# Circuit_Etudiant_2023.net
KiCad netlist of a schematic drawn in Altium Designer
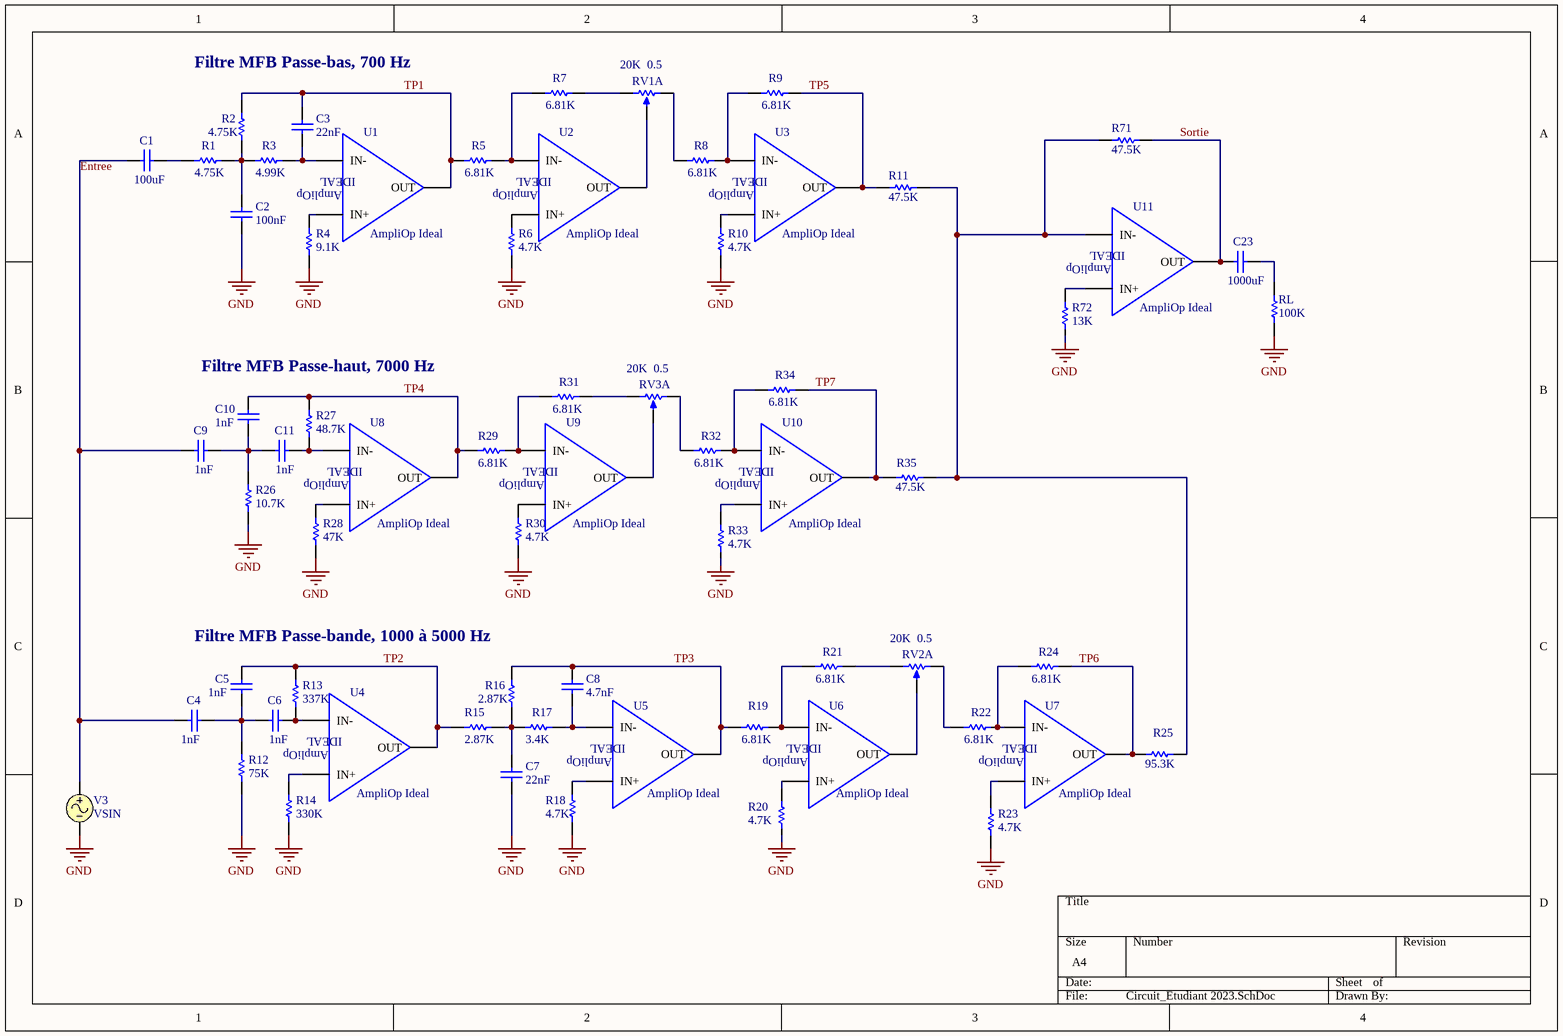
[diagram p0: Circuit_Etudiant 2023.SchDoc]

(export (version "E")
  (design (tool "Eeschema 10.0.6"))
  (components
    (comp (ref "C1")
      (value "100uF")
      (footprint "RAD-0.3")
      (description "Capacitor")
      (fields (field (name "Comment") "Cap") (field (name "PUBLISHER") "Altium Limited"))
      (libsource (lib "Miscellaneous Devices") (part "Cap"))
    )
    (comp (ref "C2")
      (value "100nF")
      (footprint "RAD-0.3")
      (description "Capacitor")
      (fields (field (name "Comment") "Cap") (field (name "PUBLISHER") "Altium Limited"))
      (libsource (lib "Miscellaneous Devices") (part "Cap"))
    )
    (comp (ref "C3")
      (value "22nF")
      (footprint "RAD-0.3")
      (description "Capacitor")
      (fields (field (name "Comment") "Cap") (field (name "PUBLISHER") "Altium Limited"))
      (libsource (lib "Miscellaneous Devices") (part "Cap"))
    )
    (comp (ref "C4")
      (value "1nF")
      (footprint "RAD-0.3")
      (description "Capacitor")
      (fields (field (name "Comment") "Cap") (field (name "PUBLISHER") "Altium Limited"))
      (libsource (lib "Miscellaneous Devices") (part "Cap"))
    )
    (comp (ref "C5")
      (value "1nF")
      (footprint "RAD-0.3")
      (description "Capacitor")
      (fields (field (name "Comment") "Cap") (field (name "PUBLISHER") "Altium Limited"))
      (libsource (lib "Miscellaneous Devices") (part "Cap"))
    )
    (comp (ref "C6")
      (value "1nF")
      (footprint "RAD-0.3")
      (description "Capacitor")
      (fields (field (name "Comment") "Cap") (field (name "PUBLISHER") "Altium Limited"))
      (libsource (lib "Miscellaneous Devices") (part "Cap"))
    )
    (comp (ref "C7")
      (value "22nF")
      (footprint "RAD-0.3")
      (description "Capacitor")
      (fields (field (name "Comment") "Cap") (field (name "PUBLISHER") "Altium Limited"))
      (libsource (lib "Miscellaneous Devices") (part "Cap"))
    )
    (comp (ref "C8")
      (value "4.7nF")
      (footprint "RAD-0.3")
      (description "Capacitor")
      (fields (field (name "Comment") "Cap") (field (name "PUBLISHER") "Altium Limited"))
      (libsource (lib "Miscellaneous Devices") (part "Cap"))
    )
    (comp (ref "C9")
      (value "1nF")
      (footprint "RAD-0.3")
      (description "Capacitor")
      (fields (field (name "Comment") "Cap") (field (name "PUBLISHER") "Altium Limited"))
      (libsource (lib "Miscellaneous Devices") (part "Cap"))
    )
    (comp (ref "C10")
      (value "1nF")
      (footprint "RAD-0.3")
      (description "Capacitor")
      (fields (field (name "Comment") "Cap") (field (name "PUBLISHER") "Altium Limited"))
      (libsource (lib "Miscellaneous Devices") (part "Cap"))
    )
    (comp (ref "C11")
      (value "1nF")
      (footprint "RAD-0.3")
      (description "Capacitor")
      (fields (field (name "Comment") "Cap") (field (name "PUBLISHER") "Altium Limited"))
      (libsource (lib "Miscellaneous Devices") (part "Cap"))
    )
    (comp (ref "C23")
      (value "1000uF")
      (footprint "RAD-0.3")
      (description "Capacitor")
      (fields (field (name "Comment") "Cap") (field (name "PUBLISHER") "Altium Limited"))
      (libsource (lib "Miscellaneous Devices") (part "Cap"))
    )
    (comp (ref "R1")
      (value "4.75K")
      (footprint "AXIAL-0.3")
      (description "Resistor")
      (fields (field (name "Comment") "Res1") (field (name "PUBLISHER") "Altium Limited"))
      (libsource (lib "Miscellaneous Devices") (part "Res1"))
    )
    (comp (ref "R2")
      (value "4.75K")
      (footprint "AXIAL-0.3")
      (description "Resistor")
      (fields (field (name "Comment") "Res1") (field (name "PUBLISHER") "Altium Limited"))
      (libsource (lib "Miscellaneous Devices") (part "Res1"))
    )
    (comp (ref "R3")
      (value "4.99K")
      (footprint "AXIAL-0.3")
      (description "Resistor")
      (fields (field (name "Comment") "Res1") (field (name "PUBLISHER") "Altium Limited"))
      (libsource (lib "Miscellaneous Devices") (part "Res1"))
    )
    (comp (ref "R4")
      (value "9.1K")
      (footprint "AXIAL-0.3")
      (description "Resistor")
      (fields (field (name "Comment") "Res1") (field (name "PUBLISHER") "Altium Limited"))
      (libsource (lib "Miscellaneous Devices") (part "Res1"))
    )
    (comp (ref "R5")
      (value "6.81K")
      (footprint "AXIAL-0.3")
      (description "Resistor")
      (fields (field (name "Comment") "Res1") (field (name "PUBLISHER") "Altium Limited"))
      (libsource (lib "Miscellaneous Devices") (part "Res1"))
    )
    (comp (ref "R6")
      (value "4.7K")
      (footprint "AXIAL-0.3")
      (description "Resistor")
      (fields (field (name "Comment") "Res1") (field (name "PUBLISHER") "Altium Limited"))
      (libsource (lib "Miscellaneous Devices") (part "Res1"))
    )
    (comp (ref "R7")
      (value "6.81K")
      (footprint "AXIAL-0.3")
      (description "Resistor")
      (fields (field (name "Comment") "Res1") (field (name "PUBLISHER") "Altium Limited"))
      (libsource (lib "Miscellaneous Devices") (part "Res1"))
    )
    (comp (ref "R8")
      (value "6.81K")
      (footprint "AXIAL-0.3")
      (description "Resistor")
      (fields (field (name "Comment") "Res1") (field (name "PUBLISHER") "Altium Limited"))
      (libsource (lib "Miscellaneous Devices") (part "Res1"))
    )
    (comp (ref "R9")
      (value "6.81K")
      (footprint "AXIAL-0.3")
      (description "Resistor")
      (fields (field (name "Comment") "Res1") (field (name "PUBLISHER") "Altium Limited"))
      (libsource (lib "Miscellaneous Devices") (part "Res1"))
    )
    (comp (ref "R10")
      (value "4.7K")
      (footprint "AXIAL-0.3")
      (description "Resistor")
      (fields (field (name "Comment") "Res1") (field (name "PUBLISHER") "Altium Limited"))
      (libsource (lib "Miscellaneous Devices") (part "Res1"))
    )
    (comp (ref "R11")
      (value "47.5K")
      (footprint "AXIAL-0.3")
      (description "Resistor")
      (fields (field (name "Comment") "Res1") (field (name "PUBLISHER") "Altium Limited"))
      (libsource (lib "Miscellaneous Devices") (part "Res1"))
    )
    (comp (ref "R12")
      (value "75K")
      (footprint "AXIAL-0.3")
      (description "Resistor")
      (fields (field (name "Comment") "Res1") (field (name "PUBLISHER") "Altium Limited"))
      (libsource (lib "Miscellaneous Devices") (part "Res1"))
    )
    (comp (ref "R13")
      (value "337K")
      (footprint "AXIAL-0.3")
      (description "Resistor")
      (fields (field (name "Comment") "Res1") (field (name "PUBLISHER") "Altium Limited"))
      (libsource (lib "Miscellaneous Devices") (part "Res1"))
    )
    (comp (ref "R14")
      (value "330K")
      (footprint "AXIAL-0.3")
      (description "Resistor")
      (fields (field (name "Comment") "Res1") (field (name "PUBLISHER") "Altium Limited"))
      (libsource (lib "Miscellaneous Devices") (part "Res1"))
    )
    (comp (ref "R15")
      (value "2.87K")
      (footprint "AXIAL-0.3")
      (description "Resistor")
      (fields (field (name "Comment") "Res1") (field (name "PUBLISHER") "Altium Limited"))
      (libsource (lib "Miscellaneous Devices") (part "Res1"))
    )
    (comp (ref "R16")
      (value "2.87K")
      (footprint "AXIAL-0.3")
      (description "Resistor")
      (fields (field (name "Comment") "Res1") (field (name "PUBLISHER") "Altium Limited"))
      (libsource (lib "Miscellaneous Devices") (part "Res1"))
    )
    (comp (ref "R17")
      (value "3.4K")
      (footprint "AXIAL-0.3")
      (description "Resistor")
      (fields (field (name "Comment") "Res1") (field (name "PUBLISHER") "Altium Limited"))
      (libsource (lib "Miscellaneous Devices") (part "Res1"))
    )
    (comp (ref "R18")
      (value "4.7K")
      (footprint "AXIAL-0.3")
      (description "Resistor")
      (fields (field (name "Comment") "Res1") (field (name "PUBLISHER") "Altium Limited"))
      (libsource (lib "Miscellaneous Devices") (part "Res1"))
    )
    (comp (ref "R19")
      (value "6.81K")
      (footprint "AXIAL-0.3")
      (description "Resistor")
      (fields (field (name "Comment") "Res1") (field (name "PUBLISHER") "Altium Limited"))
      (libsource (lib "Miscellaneous Devices") (part "Res1"))
    )
    (comp (ref "R20")
      (value "4.7K")
      (footprint "AXIAL-0.3")
      (description "Resistor")
      (fields (field (name "Comment") "Res1") (field (name "PUBLISHER") "Altium Limited"))
      (libsource (lib "Miscellaneous Devices") (part "Res1"))
    )
    (comp (ref "R21")
      (value "6.81K")
      (footprint "AXIAL-0.3")
      (description "Resistor")
      (fields (field (name "Comment") "Res1") (field (name "PUBLISHER") "Altium Limited"))
      (libsource (lib "Miscellaneous Devices") (part "Res1"))
    )
    (comp (ref "R22")
      (value "6.81K")
      (footprint "AXIAL-0.3")
      (description "Resistor")
      (fields (field (name "Comment") "Res1") (field (name "PUBLISHER") "Altium Limited"))
      (libsource (lib "Miscellaneous Devices") (part "Res1"))
    )
    (comp (ref "R23")
      (value "4.7K")
      (footprint "AXIAL-0.3")
      (description "Resistor")
      (fields (field (name "Comment") "Res1") (field (name "PUBLISHER") "Altium Limited"))
      (libsource (lib "Miscellaneous Devices") (part "Res1"))
    )
    (comp (ref "R24")
      (value "6.81K")
      (footprint "AXIAL-0.3")
      (description "Resistor")
      (fields (field (name "Comment") "Res1") (field (name "PUBLISHER") "Altium Limited"))
      (libsource (lib "Miscellaneous Devices") (part "Res1"))
    )
    (comp (ref "R25")
      (value "95.3K")
      (footprint "AXIAL-0.3")
      (description "Resistor")
      (fields (field (name "Comment") "Res1") (field (name "PUBLISHER") "Altium Limited"))
      (libsource (lib "Miscellaneous Devices") (part "Res1"))
    )
    (comp (ref "R26")
      (value "10.7K")
      (footprint "AXIAL-0.3")
      (description "Resistor")
      (fields (field (name "Comment") "Res1") (field (name "PUBLISHER") "Altium Limited"))
      (libsource (lib "Miscellaneous Devices") (part "Res1"))
    )
    (comp (ref "R27")
      (value "48.7K")
      (footprint "AXIAL-0.3")
      (description "Resistor")
      (fields (field (name "Comment") "Res1") (field (name "PUBLISHER") "Altium Limited"))
      (libsource (lib "Miscellaneous Devices") (part "Res1"))
    )
    (comp (ref "R28")
      (value "47K")
      (footprint "AXIAL-0.3")
      (description "Resistor")
      (fields (field (name "Comment") "Res1") (field (name "PUBLISHER") "Altium Limited"))
      (libsource (lib "Miscellaneous Devices") (part "Res1"))
    )
    (comp (ref "R29")
      (value "6.81K")
      (footprint "AXIAL-0.3")
      (description "Resistor")
      (fields (field (name "Comment") "Res1") (field (name "PUBLISHER") "Altium Limited"))
      (libsource (lib "Miscellaneous Devices") (part "Res1"))
    )
    (comp (ref "R30")
      (value "4.7K")
      (footprint "AXIAL-0.3")
      (description "Resistor")
      (fields (field (name "Comment") "Res1") (field (name "PUBLISHER") "Altium Limited"))
      (libsource (lib "Miscellaneous Devices") (part "Res1"))
    )
    (comp (ref "R31")
      (value "6.81K")
      (footprint "AXIAL-0.3")
      (description "Resistor")
      (fields (field (name "Comment") "Res1") (field (name "PUBLISHER") "Altium Limited"))
      (libsource (lib "Miscellaneous Devices") (part "Res1"))
    )
    (comp (ref "R32")
      (value "6.81K")
      (footprint "AXIAL-0.3")
      (description "Resistor")
      (fields (field (name "Comment") "Res1") (field (name "PUBLISHER") "Altium Limited"))
      (libsource (lib "Miscellaneous Devices") (part "Res1"))
    )
    (comp (ref "R33")
      (value "4.7K")
      (footprint "AXIAL-0.3")
      (description "Resistor")
      (fields (field (name "Comment") "Res1") (field (name "PUBLISHER") "Altium Limited"))
      (libsource (lib "Miscellaneous Devices") (part "Res1"))
    )
    (comp (ref "R34")
      (value "6.81K")
      (footprint "AXIAL-0.3")
      (description "Resistor")
      (fields (field (name "Comment") "Res1") (field (name "PUBLISHER") "Altium Limited"))
      (libsource (lib "Miscellaneous Devices") (part "Res1"))
    )
    (comp (ref "R35")
      (value "47.5K")
      (footprint "AXIAL-0.3")
      (description "Resistor")
      (fields (field (name "Comment") "Res1") (field (name "PUBLISHER") "Altium Limited"))
      (libsource (lib "Miscellaneous Devices") (part "Res1"))
    )
    (comp (ref "R71")
      (value "47.5K")
      (footprint "AXIAL-0.3")
      (description "Resistor")
      (fields (field (name "Comment") "Res1") (field (name "PUBLISHER") "Altium Limited"))
      (libsource (lib "Miscellaneous Devices") (part "Res1"))
    )
    (comp (ref "R72")
      (value "13K")
      (footprint "AXIAL-0.3")
      (description "Resistor")
      (fields (field (name "Comment") "Res1") (field (name "PUBLISHER") "Altium Limited"))
      (libsource (lib "Miscellaneous Devices") (part "Res1"))
    )
    (comp (ref "RL")
      (value "100K")
      (footprint "AXIAL-0.3")
      (description "Resistor")
      (fields (field (name "Comment") "Res1") (field (name "PUBLISHER") "Altium Limited"))
      (libsource (lib "Miscellaneous Devices") (part "Res1"))
    )
    (comp (ref "RV1A")
      (value "20K")
      (footprint "VR5")
      (description "Potentiometer")
      (fields
        (field (name "SET POSITION") "0.5")
        (field (name "Comment") "RPot")
        (field (name "PUBLISHER") "Altium Limited")
      )
      (libsource (lib "Miscellaneous Devices") (part "RPot"))
    )
    (comp (ref "RV2A")
      (value "20K")
      (footprint "VR5")
      (description "Potentiometer")
      (fields
        (field (name "SET POSITION") "0.5")
        (field (name "Comment") "RPot")
        (field (name "PUBLISHER") "Altium Limited")
      )
      (libsource (lib "Miscellaneous Devices") (part "RPot"))
    )
    (comp (ref "RV3A")
      (value "20K")
      (footprint "VR5")
      (description "Potentiometer")
      (fields
        (field (name "SET POSITION") "0.5")
        (field (name "Comment") "RPot")
        (field (name "PUBLISHER") "Altium Limited")
      )
      (libsource (lib "Miscellaneous Devices") (part "RPot"))
    )
    (comp (ref "U1") (value "AmpliOp Ideal") (libsource (lib "Librarie_S2") (part "AmpliOp_ideal")))
    (comp (ref "U2") (value "AmpliOp Ideal") (libsource (lib "Librarie_S2") (part "AmpliOp_ideal")))
    (comp (ref "U3") (value "AmpliOp Ideal") (libsource (lib "Librarie_S2") (part "AmpliOp_ideal")))
    (comp (ref "U4") (value "AmpliOp Ideal") (libsource (lib "Librarie_S2") (part "AmpliOp_ideal")))
    (comp (ref "U5") (value "AmpliOp Ideal") (libsource (lib "Librarie_S2") (part "AmpliOp_ideal")))
    (comp (ref "U6") (value "AmpliOp Ideal") (libsource (lib "Librarie_S2") (part "AmpliOp_ideal")))
    (comp (ref "U7") (value "AmpliOp Ideal") (libsource (lib "Librarie_S2") (part "AmpliOp_ideal")))
    (comp (ref "U8") (value "AmpliOp Ideal") (libsource (lib "Librarie_S2") (part "AmpliOp_ideal")))
    (comp (ref "U9") (value "AmpliOp Ideal") (libsource (lib "Librarie_S2") (part "AmpliOp_ideal")))
    (comp (ref "U10") (value "AmpliOp Ideal") (libsource (lib "Librarie_S2") (part "AmpliOp_ideal")))
    (comp (ref "U11") (value "AmpliOp Ideal") (libsource (lib "Librarie_S2") (part "AmpliOp_ideal")))
    (comp (ref "V3")
      (value "VSIN")
      (description "Sinusoidal Voltage Source")
      (fields (field (name "PUBLISHER") "Altium Limited"))
      (libsource (lib "Simulation Sources") (part "VSIN"))
    )
  )
  (nets
    (net (code "1") (name "/Entree") (class "Default")
      (node (ref "C1") (pin "1") (pinfunction "1_1") (pintype "passive"))
      (node (ref "C4") (pin "1") (pinfunction "1_1") (pintype "passive"))
      (node (ref "C9") (pin "1") (pinfunction "1_1") (pintype "passive"))
      (node (ref "V3") (pin "1") (pinfunction "1_1") (pintype "passive"))
    )
    (net (code "2") (name "/Sortie") (class "Default")
      (node (ref "C23") (pin "1") (pinfunction "1_1") (pintype "passive"))
      (node (ref "R71") (pin "2") (pinfunction "2_2") (pintype "passive"))
      (node (ref "U11") (pin "3") (pinfunction "OUT_3") (pintype "passive"))
    )
    (net (code "3") (name "/TP1") (class "Default")
      (node (ref "C3") (pin "1") (pinfunction "1_1") (pintype "passive"))
      (node (ref "R2") (pin "1") (pinfunction "1_1") (pintype "passive"))
      (node (ref "R5") (pin "1") (pinfunction "1_1") (pintype "passive"))
      (node (ref "U1") (pin "3") (pinfunction "OUT_3") (pintype "passive"))
    )
    (net (code "4") (name "/TP2") (class "Default")
      (node (ref "C5") (pin "1") (pinfunction "1_1") (pintype "passive"))
      (node (ref "R13") (pin "1") (pinfunction "1_1") (pintype "passive"))
      (node (ref "R15") (pin "1") (pinfunction "1_1") (pintype "passive"))
      (node (ref "U4") (pin "3") (pinfunction "OUT_3") (pintype "passive"))
    )
    (net (code "5") (name "/TP3") (class "Default")
      (node (ref "C8") (pin "1") (pinfunction "1_1") (pintype "passive"))
      (node (ref "R16") (pin "1") (pinfunction "1_1") (pintype "passive"))
      (node (ref "R19") (pin "1") (pinfunction "1_1") (pintype "passive"))
      (node (ref "U5") (pin "3") (pinfunction "OUT_3") (pintype "passive"))
    )
    (net (code "6") (name "/TP4") (class "Default")
      (node (ref "C10") (pin "1") (pinfunction "1_1") (pintype "passive"))
      (node (ref "R27") (pin "1") (pinfunction "1_1") (pintype "passive"))
      (node (ref "R29") (pin "1") (pinfunction "1_1") (pintype "passive"))
      (node (ref "U8") (pin "3") (pinfunction "OUT_3") (pintype "passive"))
    )
    (net (code "7") (name "/TP5") (class "Default")
      (node (ref "R11") (pin "1") (pinfunction "1_1") (pintype "passive"))
      (node (ref "R9") (pin "2") (pinfunction "2_2") (pintype "passive"))
      (node (ref "U3") (pin "3") (pinfunction "OUT_3") (pintype "passive"))
    )
    (net (code "8") (name "/TP6") (class "Default")
      (node (ref "R24") (pin "2") (pinfunction "2_2") (pintype "passive"))
      (node (ref "R25") (pin "1") (pinfunction "1_1") (pintype "passive"))
      (node (ref "U7") (pin "3") (pinfunction "OUT_3") (pintype "passive"))
    )
    (net (code "9") (name "/TP7") (class "Default")
      (node (ref "R34") (pin "2") (pinfunction "2_2") (pintype "passive"))
      (node (ref "R35") (pin "1") (pinfunction "1_1") (pintype "passive"))
      (node (ref "U10") (pin "3") (pinfunction "OUT_3") (pintype "passive"))
    )
    (net (code "10") (name "GND") (class "Default")
      (node (ref "C2") (pin "2") (pinfunction "2_2") (pintype "passive"))
      (node (ref "C7") (pin "2") (pinfunction "2_2") (pintype "passive"))
      (node (ref "R10") (pin "2") (pinfunction "2_2") (pintype "passive"))
      (node (ref "R12") (pin "2") (pinfunction "2_2") (pintype "passive"))
      (node (ref "R14") (pin "2") (pinfunction "2_2") (pintype "passive"))
      (node (ref "R18") (pin "2") (pinfunction "2_2") (pintype "passive"))
      (node (ref "R20") (pin "2") (pinfunction "2_2") (pintype "passive"))
      (node (ref "R23") (pin "2") (pinfunction "2_2") (pintype "passive"))
      (node (ref "R26") (pin "2") (pinfunction "2_2") (pintype "passive"))
      (node (ref "R28") (pin "2") (pinfunction "2_2") (pintype "passive"))
      (node (ref "R30") (pin "2") (pinfunction "2_2") (pintype "passive"))
      (node (ref "R33") (pin "2") (pinfunction "2_2") (pintype "passive"))
      (node (ref "R4") (pin "2") (pinfunction "2_2") (pintype "passive"))
      (node (ref "R6") (pin "2") (pinfunction "2_2") (pintype "passive"))
      (node (ref "R72") (pin "2") (pinfunction "2_2") (pintype "passive"))
      (node (ref "RL") (pin "1") (pinfunction "1_1") (pintype "passive"))
      (node (ref "V3") (pin "2") (pinfunction "2_2") (pintype "passive"))
    )
    (net (code "11") (name "Net-(C1-Pad2)") (class "Default")
      (node (ref "C1") (pin "2") (pinfunction "2_2") (pintype "passive"))
      (node (ref "R1") (pin "1") (pinfunction "1_1") (pintype "passive"))
    )
    (net (code "12") (name "Net-(C2-Pad1)") (class "Default")
      (node (ref "C2") (pin "1") (pinfunction "1_1") (pintype "passive"))
      (node (ref "R1") (pin "2") (pinfunction "2_2") (pintype "passive"))
      (node (ref "R2") (pin "2") (pinfunction "2_2") (pintype "passive"))
      (node (ref "R3") (pin "1") (pinfunction "1_1") (pintype "passive"))
    )
    (net (code "13") (name "Net-(C4-Pad2)") (class "Default")
      (node (ref "C4") (pin "2") (pinfunction "2_2") (pintype "passive"))
      (node (ref "C5") (pin "2") (pinfunction "2_2") (pintype "passive"))
      (node (ref "C6") (pin "1") (pinfunction "1_1") (pintype "passive"))
      (node (ref "R12") (pin "1") (pinfunction "1_1") (pintype "passive"))
    )
    (net (code "14") (name "Net-(C7-Pad1)") (class "Default")
      (node (ref "C7") (pin "1") (pinfunction "1_1") (pintype "passive"))
      (node (ref "R15") (pin "2") (pinfunction "2_2") (pintype "passive"))
      (node (ref "R16") (pin "2") (pinfunction "2_2") (pintype "passive"))
      (node (ref "R17") (pin "1") (pinfunction "1_1") (pintype "passive"))
    )
    (net (code "15") (name "Net-(C10-Pad2)") (class "Default")
      (node (ref "C10") (pin "2") (pinfunction "2_2") (pintype "passive"))
      (node (ref "C11") (pin "1") (pinfunction "1_1") (pintype "passive"))
      (node (ref "C9") (pin "2") (pinfunction "2_2") (pintype "passive"))
      (node (ref "R26") (pin "1") (pinfunction "1_1") (pintype "passive"))
    )
    (net (code "16") (name "Net-(C23-Pad2)") (class "Default")
      (node (ref "C23") (pin "2") (pinfunction "2_2") (pintype "passive"))
      (node (ref "RL") (pin "2") (pinfunction "2_2") (pintype "passive"))
    )
    (net (code "17") (name "Net-(RV1A-BOT)") (class "Default")
      (node (ref "R8") (pin "1") (pinfunction "1_1") (pintype "passive"))
      (node (ref "RV1A") (pin "2") (pinfunction "BOT_2") (pintype "passive"))
    )
    (net (code "18") (name "Net-(RV1A-TAP)") (class "Default")
      (node (ref "RV1A") (pin "3") (pinfunction "TAP_3") (pintype "passive"))
      (node (ref "U2") (pin "3") (pinfunction "OUT_3") (pintype "passive"))
    )
    (net (code "19") (name "Net-(RV1A-TOP)") (class "Default")
      (node (ref "R7") (pin "2") (pinfunction "2_2") (pintype "passive"))
      (node (ref "RV1A") (pin "1") (pinfunction "TOP_1") (pintype "passive"))
    )
    (net (code "20") (name "Net-(RV2A-BOT)") (class "Default")
      (node (ref "R22") (pin "1") (pinfunction "1_1") (pintype "passive"))
      (node (ref "RV2A") (pin "2") (pinfunction "BOT_2") (pintype "passive"))
    )
    (net (code "21") (name "Net-(RV2A-TAP)") (class "Default")
      (node (ref "RV2A") (pin "3") (pinfunction "TAP_3") (pintype "passive"))
      (node (ref "U6") (pin "3") (pinfunction "OUT_3") (pintype "passive"))
    )
    (net (code "22") (name "Net-(RV2A-TOP)") (class "Default")
      (node (ref "R21") (pin "2") (pinfunction "2_2") (pintype "passive"))
      (node (ref "RV2A") (pin "1") (pinfunction "TOP_1") (pintype "passive"))
    )
    (net (code "23") (name "Net-(RV3A-BOT)") (class "Default")
      (node (ref "R32") (pin "1") (pinfunction "1_1") (pintype "passive"))
      (node (ref "RV3A") (pin "2") (pinfunction "BOT_2") (pintype "passive"))
    )
    (net (code "24") (name "Net-(RV3A-TAP)") (class "Default")
      (node (ref "RV3A") (pin "3") (pinfunction "TAP_3") (pintype "passive"))
      (node (ref "U9") (pin "3") (pinfunction "OUT_3") (pintype "passive"))
    )
    (net (code "25") (name "Net-(RV3A-TOP)") (class "Default")
      (node (ref "R31") (pin "2") (pinfunction "2_2") (pintype "passive"))
      (node (ref "RV3A") (pin "1") (pinfunction "TOP_1") (pintype "passive"))
    )
    (net (code "26") (name "Net-(U1-IN+)") (class "Default")
      (node (ref "R4") (pin "1") (pinfunction "1_1") (pintype "passive"))
      (node (ref "U1") (pin "1") (pinfunction "IN+_1") (pintype "passive"))
    )
    (net (code "27") (name "Net-(U1-IN-)") (class "Default")
      (node (ref "C3") (pin "2") (pinfunction "2_2") (pintype "passive"))
      (node (ref "R3") (pin "2") (pinfunction "2_2") (pintype "passive"))
      (node (ref "U1") (pin "2") (pinfunction "IN-_2") (pintype "passive"))
    )
    (net (code "28") (name "Net-(U2-IN+)") (class "Default")
      (node (ref "R6") (pin "1") (pinfunction "1_1") (pintype "passive"))
      (node (ref "U2") (pin "1") (pinfunction "IN+_1") (pintype "passive"))
    )
    (net (code "29") (name "Net-(U2-IN-)") (class "Default")
      (node (ref "R5") (pin "2") (pinfunction "2_2") (pintype "passive"))
      (node (ref "R7") (pin "1") (pinfunction "1_1") (pintype "passive"))
      (node (ref "U2") (pin "2") (pinfunction "IN-_2") (pintype "passive"))
    )
    (net (code "30") (name "Net-(U3-IN+)") (class "Default")
      (node (ref "R10") (pin "1") (pinfunction "1_1") (pintype "passive"))
      (node (ref "U3") (pin "1") (pinfunction "IN+_1") (pintype "passive"))
    )
    (net (code "31") (name "Net-(U3-IN-)") (class "Default")
      (node (ref "R8") (pin "2") (pinfunction "2_2") (pintype "passive"))
      (node (ref "R9") (pin "1") (pinfunction "1_1") (pintype "passive"))
      (node (ref "U3") (pin "2") (pinfunction "IN-_2") (pintype "passive"))
    )
    (net (code "32") (name "Net-(U4-IN+)") (class "Default")
      (node (ref "R14") (pin "1") (pinfunction "1_1") (pintype "passive"))
      (node (ref "U4") (pin "1") (pinfunction "IN+_1") (pintype "passive"))
    )
    (net (code "33") (name "Net-(U4-IN-)") (class "Default")
      (node (ref "C6") (pin "2") (pinfunction "2_2") (pintype "passive"))
      (node (ref "R13") (pin "2") (pinfunction "2_2") (pintype "passive"))
      (node (ref "U4") (pin "2") (pinfunction "IN-_2") (pintype "passive"))
    )
    (net (code "34") (name "Net-(U5-IN+)") (class "Default")
      (node (ref "R18") (pin "1") (pinfunction "1_1") (pintype "passive"))
      (node (ref "U5") (pin "1") (pinfunction "IN+_1") (pintype "passive"))
    )
    (net (code "35") (name "Net-(U5-IN-)") (class "Default")
      (node (ref "C8") (pin "2") (pinfunction "2_2") (pintype "passive"))
      (node (ref "R17") (pin "2") (pinfunction "2_2") (pintype "passive"))
      (node (ref "U5") (pin "2") (pinfunction "IN-_2") (pintype "passive"))
    )
    (net (code "36") (name "Net-(U6-IN+)") (class "Default")
      (node (ref "R20") (pin "1") (pinfunction "1_1") (pintype "passive"))
      (node (ref "U6") (pin "1") (pinfunction "IN+_1") (pintype "passive"))
    )
    (net (code "37") (name "Net-(U6-IN-)") (class "Default")
      (node (ref "R19") (pin "2") (pinfunction "2_2") (pintype "passive"))
      (node (ref "R21") (pin "1") (pinfunction "1_1") (pintype "passive"))
      (node (ref "U6") (pin "2") (pinfunction "IN-_2") (pintype "passive"))
    )
    (net (code "38") (name "Net-(U7-IN+)") (class "Default")
      (node (ref "R23") (pin "1") (pinfunction "1_1") (pintype "passive"))
      (node (ref "U7") (pin "1") (pinfunction "IN+_1") (pintype "passive"))
    )
    (net (code "39") (name "Net-(U7-IN-)") (class "Default")
      (node (ref "R22") (pin "2") (pinfunction "2_2") (pintype "passive"))
      (node (ref "R24") (pin "1") (pinfunction "1_1") (pintype "passive"))
      (node (ref "U7") (pin "2") (pinfunction "IN-_2") (pintype "passive"))
    )
    (net (code "40") (name "Net-(U8-IN+)") (class "Default")
      (node (ref "R28") (pin "1") (pinfunction "1_1") (pintype "passive"))
      (node (ref "U8") (pin "1") (pinfunction "IN+_1") (pintype "passive"))
    )
    (net (code "41") (name "Net-(U8-IN-)") (class "Default")
      (node (ref "C11") (pin "2") (pinfunction "2_2") (pintype "passive"))
      (node (ref "R27") (pin "2") (pinfunction "2_2") (pintype "passive"))
      (node (ref "U8") (pin "2") (pinfunction "IN-_2") (pintype "passive"))
    )
    (net (code "42") (name "Net-(U9-IN+)") (class "Default")
      (node (ref "R30") (pin "1") (pinfunction "1_1") (pintype "passive"))
      (node (ref "U9") (pin "1") (pinfunction "IN+_1") (pintype "passive"))
    )
    (net (code "43") (name "Net-(U9-IN-)") (class "Default")
      (node (ref "R29") (pin "2") (pinfunction "2_2") (pintype "passive"))
      (node (ref "R31") (pin "1") (pinfunction "1_1") (pintype "passive"))
      (node (ref "U9") (pin "2") (pinfunction "IN-_2") (pintype "passive"))
    )
    (net (code "44") (name "Net-(U10-IN+)") (class "Default")
      (node (ref "R33") (pin "1") (pinfunction "1_1") (pintype "passive"))
      (node (ref "U10") (pin "1") (pinfunction "IN+_1") (pintype "passive"))
    )
    (net (code "45") (name "Net-(U10-IN-)") (class "Default")
      (node (ref "R32") (pin "2") (pinfunction "2_2") (pintype "passive"))
      (node (ref "R34") (pin "1") (pinfunction "1_1") (pintype "passive"))
      (node (ref "U10") (pin "2") (pinfunction "IN-_2") (pintype "passive"))
    )
    (net (code "46") (name "Net-(U11-IN+)") (class "Default")
      (node (ref "R72") (pin "1") (pinfunction "1_1") (pintype "passive"))
      (node (ref "U11") (pin "1") (pinfunction "IN+_1") (pintype "passive"))
    )
    (net (code "47") (name "Net-(U11-IN-)") (class "Default")
      (node (ref "R11") (pin "2") (pinfunction "2_2") (pintype "passive"))
      (node (ref "R25") (pin "2") (pinfunction "2_2") (pintype "passive"))
      (node (ref "R35") (pin "2") (pinfunction "2_2") (pintype "passive"))
      (node (ref "R71") (pin "1") (pinfunction "1_1") (pintype "passive"))
      (node (ref "U11") (pin "2") (pinfunction "IN-_2") (pintype "passive"))
    )
  )
)
